# LB_o4_Vibration_Motor-v03_rev2.net
KiCad netlist of a schematic drawn in EAGLE
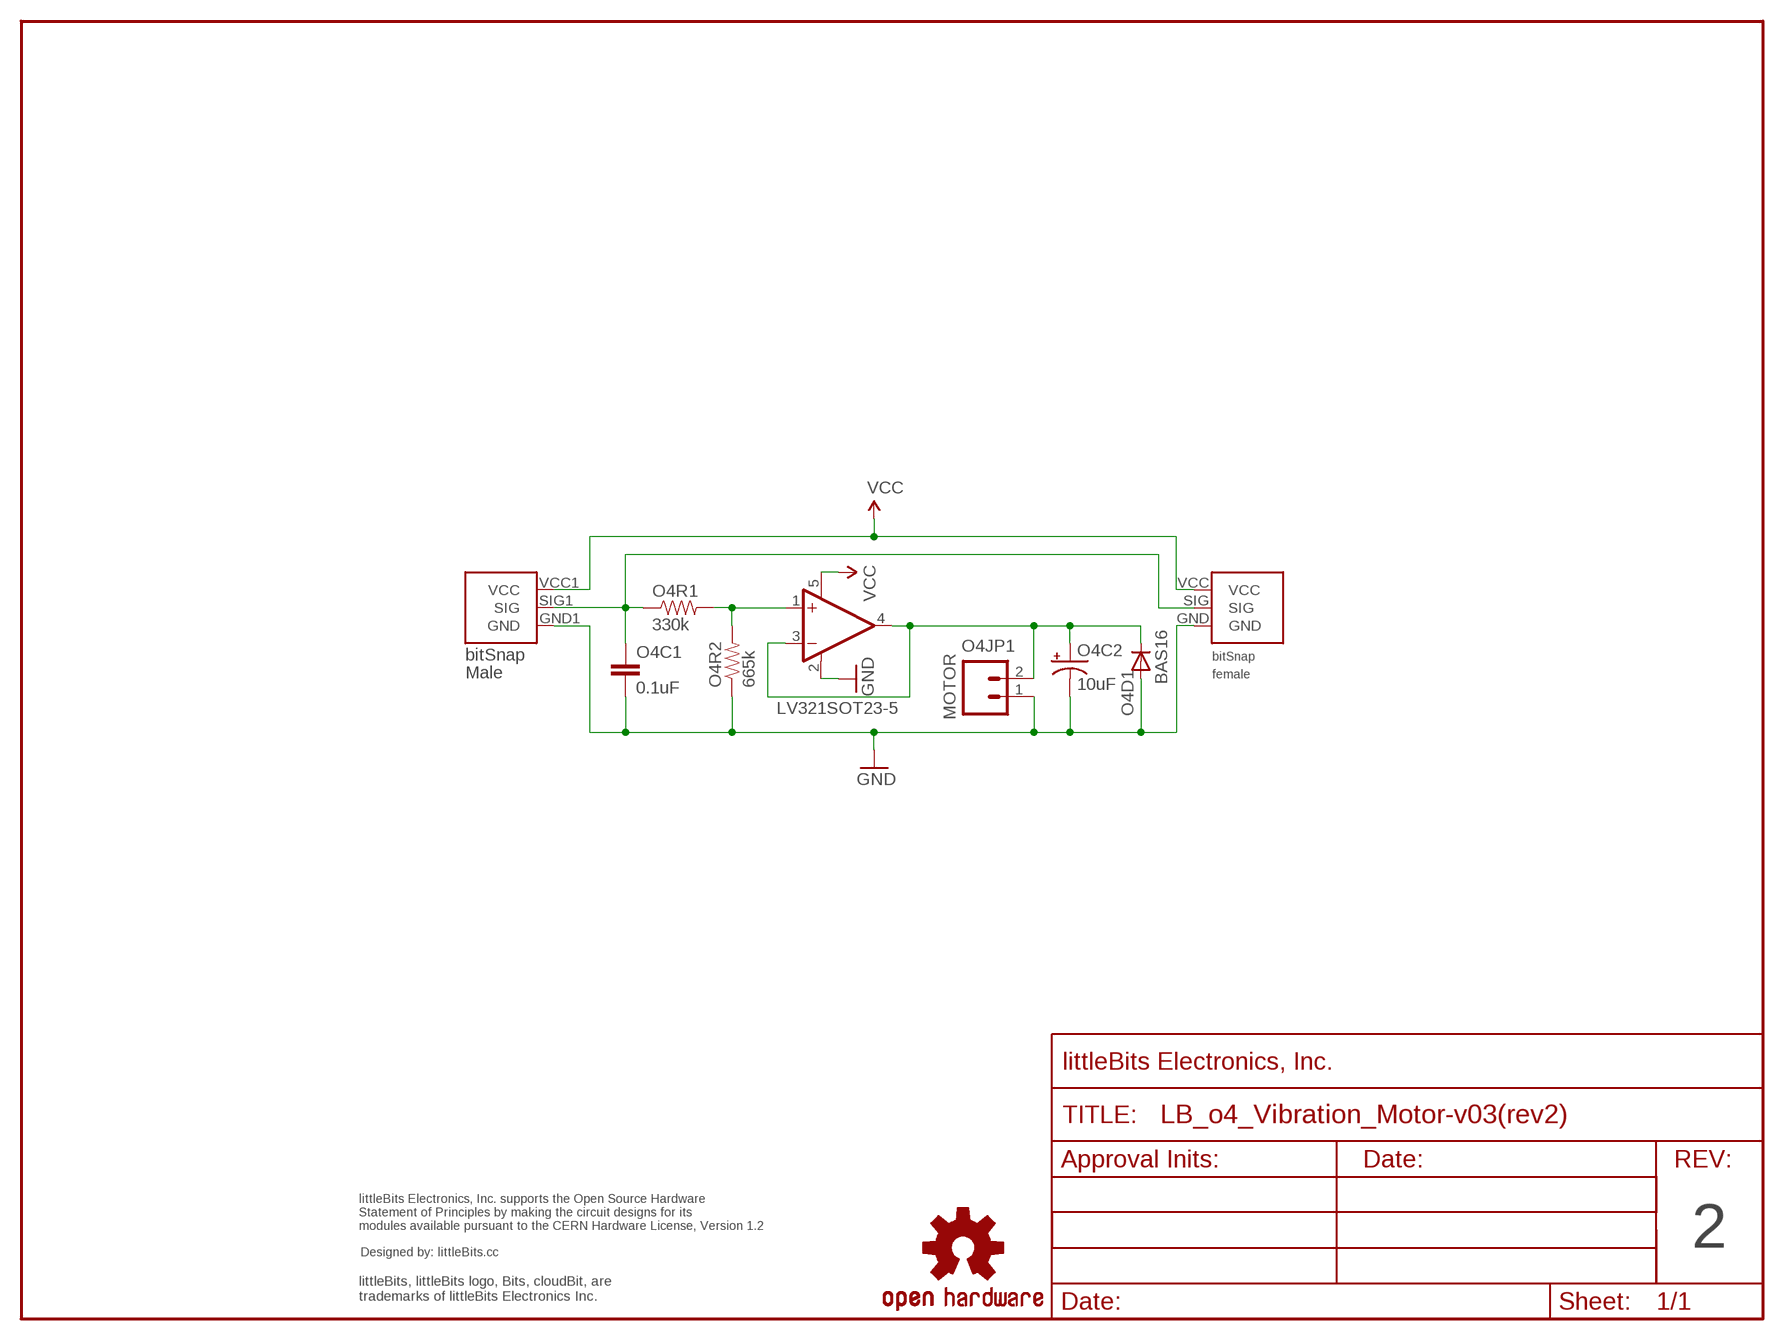
[diagram p0: schematic, sheet 1]

(export (version "E")
  (design (tool "Eeschema 10.0.6"))
  (components
    (comp (ref "O4BSF1")
      (value "BITSNAP_V03_FEMALE")
      (footprint "eagle-import:BITSNAP_V03_FEMALE")
      (libsource (lib "eagle-import") (part "BITSNAP_V03_FEMALE"))
    )
    (comp (ref "O4BSM1")
      (value "BITSNAP_V03_MALE")
      (footprint "eagle-import:BITSNAP_V03_MALE")
      (libsource (lib "eagle-import") (part "BITSNAP_V03_MALE"))
    )
    (comp (ref "O4C1")
      (value "0.1uF")
      (footprint "eagle-import:0603-CAP")
      (libsource (lib "eagle-import") (part "CAP0603-CAP"))
    )
    (comp (ref "O4C2")
      (value "10uF")
      (footprint "eagle-import:EIA3216")
      (libsource (lib "eagle-import") (part "CAP_POL1206"))
    )
    (comp (ref "O4D1")
      (value "BAS16")
      (footprint "eagle-import:SOT23-3")
      (libsource (lib "eagle-import") (part "DIODESOT23"))
    )
    (comp (ref "O4JP1")
      (value "MOTOR")
      (footprint "eagle-import:JST-MICRO_2P")
      (libsource (lib "eagle-import") (part "JST-MICRO-2P"))
    )
    (comp (ref "O4R1")
      (value "330k")
      (footprint "eagle-import:0603-RES")
      (libsource (lib "eagle-import") (part "RESISTOR0603-RES"))
    )
    (comp (ref "O4R2")
      (value "665k")
      (footprint "eagle-import:0603-RES")
      (libsource (lib "eagle-import") (part "RESISTOR0603-RES"))
    )
    (comp (ref "O4U1")
      (value "LV321SOT23-5")
      (footprint "eagle-import:SOT23-5")
      (libsource (lib "eagle-import") (part "LV321SOT23-5"))
    )
    (comp (ref "U$1")
      (value "OSHWCREDIT")
      (footprint "eagle-import:OSHWCREDIT")
      (libsource (lib "eagle-import") (part "OSHWCREDIT"))
    )
    (comp (ref "U$2")
      (value "FRAME-LETTER-OHWOHW")
      (footprint "eagle-import:FABDWG01-OHW")
      (libsource (lib "eagle-import") (part "FRAME-LETTER-OHWOHW"))
    )
    (comp (ref "U$5")
      (value "OSHW-LOGOL")
      (footprint "eagle-import:OSHW-LOGO-L")
      (libsource (lib "eagle-import") (part "OSHW-LOGOL"))
    )
  )
  (nets
    (net (code "1") (name "GND") (class "Default")
      (node (ref "O4BSF1") (pin "GND") (pinfunction "GND_GND") (pintype "bidirectional"))
      (node (ref "O4BSM1") (pin "GND1") (pinfunction "GND_GND1") (pintype "bidirectional"))
      (node (ref "O4C1") (pin "2") (pinfunction "2_2") (pintype "passive"))
      (node (ref "O4C2") (pin "C") (pinfunction "-_C") (pintype "passive"))
      (node (ref "O4D1") (pin "1") (pinfunction "A_1") (pintype "passive"))
      (node (ref "O4JP1") (pin "1") (pinfunction "1_1") (pintype "passive"))
      (node (ref "O4R2") (pin "1") (pinfunction "1_1") (pintype "passive"))
      (node (ref "O4U1") (pin "2") (pinfunction "V-_2") (pintype "power_in"))
    )
    (net (code "2") (name "Net-(O4BSM1-SIG)") (class "Default")
      (node (ref "O4BSF1") (pin "SIG") (pinfunction "SIG_SIG") (pintype "bidirectional"))
      (node (ref "O4BSM1") (pin "SIG1") (pinfunction "SIG_SIG1") (pintype "bidirectional"))
      (node (ref "O4C1") (pin "1") (pinfunction "1_1") (pintype "passive"))
      (node (ref "O4R1") (pin "1") (pinfunction "1_1") (pintype "passive"))
    )
    (net (code "3") (name "Net-(O4C2-+)") (class "Default")
      (node (ref "O4C2") (pin "A") (pinfunction "+_A") (pintype "passive"))
      (node (ref "O4D1") (pin "3") (pinfunction "C_3") (pintype "passive"))
      (node (ref "O4JP1") (pin "2") (pinfunction "2_2") (pintype "passive"))
      (node (ref "O4U1") (pin "3") (pinfunction "-IN_3") (pintype "input"))
      (node (ref "O4U1") (pin "4") (pinfunction "OUT_4") (pintype "output"))
    )
    (net (code "4") (name "Net-(O4U1-+IN)") (class "Default")
      (node (ref "O4R1") (pin "2") (pinfunction "2_2") (pintype "passive"))
      (node (ref "O4R2") (pin "2") (pinfunction "2_2") (pintype "passive"))
      (node (ref "O4U1") (pin "1") (pinfunction "+IN_1") (pintype "input"))
    )
    (net (code "5") (name "VCC") (class "Default")
      (node (ref "O4BSF1") (pin "VCC") (pinfunction "VCC_VCC") (pintype "bidirectional"))
      (node (ref "O4BSM1") (pin "VCC1") (pinfunction "VCC_VCC1") (pintype "bidirectional"))
      (node (ref "O4U1") (pin "5") (pinfunction "V+_5") (pintype "power_in"))
    )
  )
)
